# USB_trans.net
KiCad netlist of a schematic drawn in Altium Designer
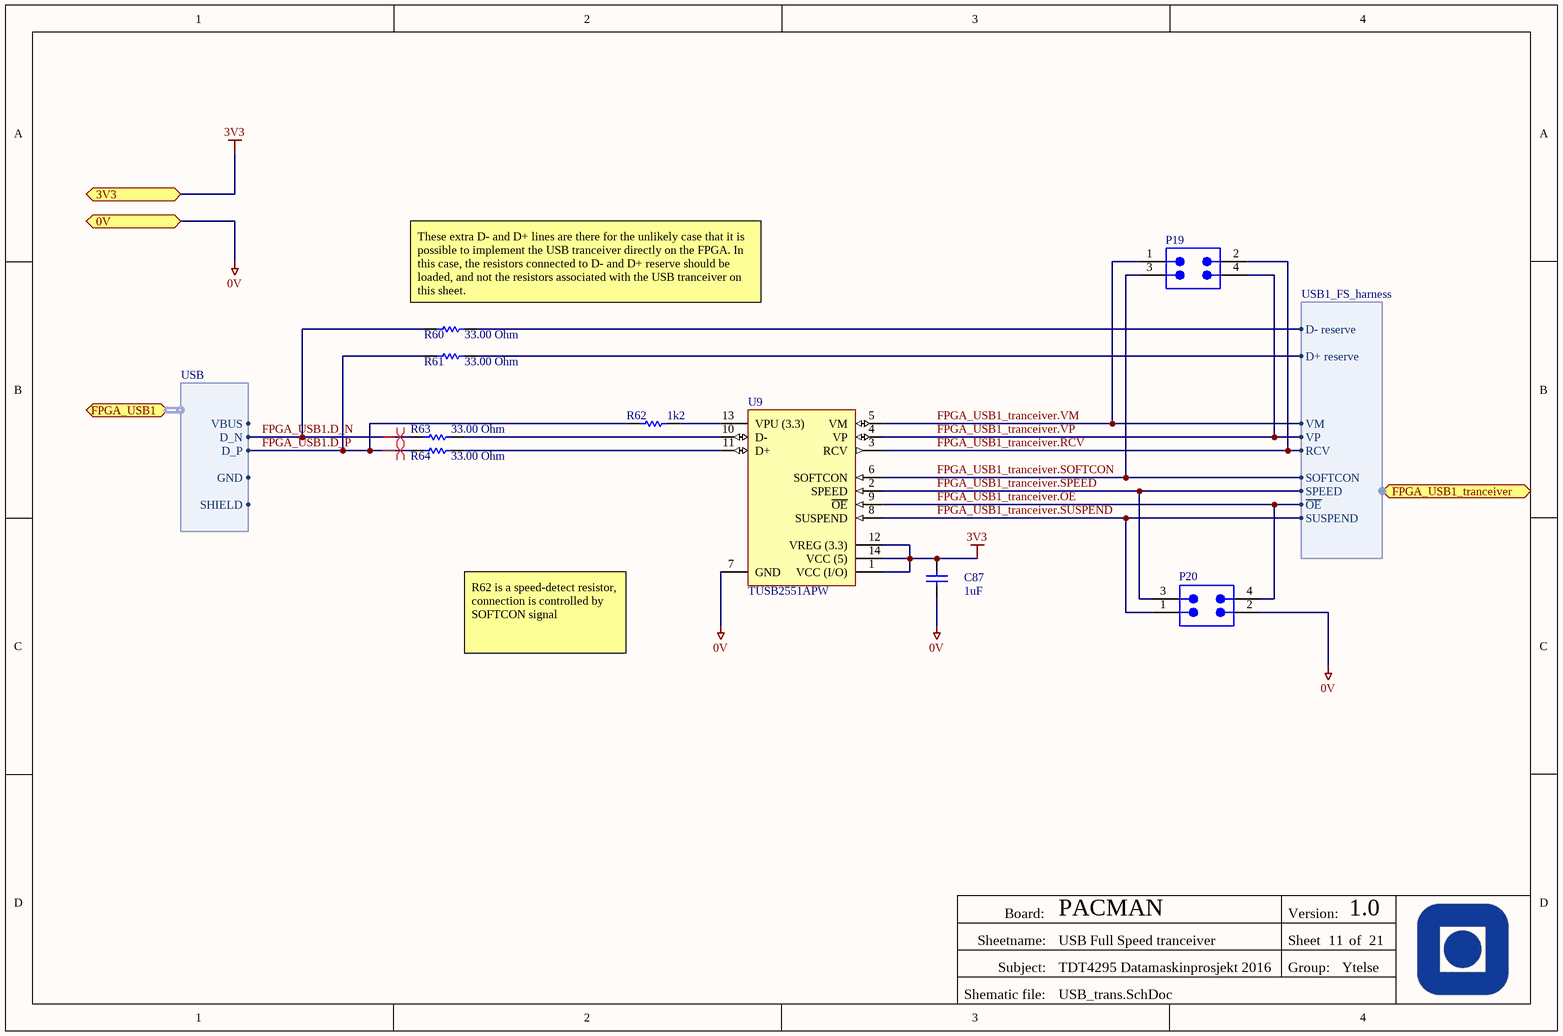
[diagram p0: USB_trans.SchDoc]

(export (version "E")
  (design (tool "Eeschema 10.0.6"))
  (components
    (comp (ref "C87")
      (value "1uF")
      (footprint "CAPC0603(1608)100_N")
      (description "CAP 1uF 16V ±5% 0603 (1608 Metric) Thickness 1mm SMD")
      (fields (field (name "TOLERANCE") "Â±5%") (field (name "Comment") "CAP 1uF 16V 0603(1608)"))
      (libsource (lib "Altium Content Vault") (part "CMP-1035-02736-1"))
    )
    (comp (ref "P19")
      (value "PH2542-4-SPGRH-6-3")
      (footprint "PCE-PH2542-4-SPGRH-6-3_V")
      (description "Male Header, Pitch 2.54mm, 2x2 Position, Mated Height 6mm, Tail Length 3mm")
      (fields (field (name "MANUFACTURER") "Pinchao Electronic"))
      (libsource (lib "") (part "PCE-HDR-2P-M-R4_1"))
    )
    (comp (ref "P20")
      (value "PH2542-4-SPGRH-6-3")
      (footprint "PCE-PH2542-4-SPGRH-6-3_V")
      (description "Male Header, Pitch 2.54mm, 2x2 Position, Mated Height 6mm, Tail Length 3mm")
      (fields (field (name "MANUFACTURER") "Pinchao Electronic"))
      (libsource (lib "Altium Content Vault") (part "PCE-HDR-2P-M-R4"))
    )
    (comp (ref "R60")
      (value "33.00 Ohm")
      (footprint "RESC0603(1608)_M")
      (description "33R 0.1W 5% 0603 (1608 Metric)  SMD")
      (fields (field (name "TOLERANCE") "5 %") (field (name "POWER") "0.1 W"))
      (libsource (lib "Altium Content Vault") (part "CMP-1012-00038-1"))
    )
    (comp (ref "R61")
      (value "33.00 Ohm")
      (footprint "RESC0603(1608)_M")
      (description "33R 0.1W 5% 0603 (1608 Metric)  SMD")
      (fields (field (name "TOLERANCE") "5 %") (field (name "POWER") "0.1 W"))
      (libsource (lib "Altium Content Vault") (part "CMP-1012-00038-1"))
    )
    (comp (ref "R62")
      (value "1k2")
      (footprint "RESC0603(1608)_M")
      (description "1K2 0.1W 1% 0603 (1608 Metric)  SMD")
      (fields (field (name "POWER") "0.1 W") (field (name "TOLERANCE") "1 %"))
      (libsource (lib "Altium Content Vault") (part "CMP-1012-00518-1"))
    )
    (comp (ref "R63")
      (value "33.00 Ohm")
      (footprint "RESC0603(1608)_M")
      (description "33R 0.1W 5% 0603 (1608 Metric)  SMD")
      (fields (field (name "TOLERANCE") "5 %") (field (name "POWER") "0.1 W"))
      (libsource (lib "Altium Content Vault") (part "CMP-1012-00038-1"))
    )
    (comp (ref "R64")
      (value "33.00 Ohm")
      (footprint "RESC0603(1608)_M")
      (description "33R 0.1W 5% 0603 (1608 Metric)  SMD")
      (fields (field (name "TOLERANCE") "5 %") (field (name "POWER") "0.1 W"))
      (libsource (lib "Altium Content Vault") (part "CMP-1012-00038-1"))
    )
    (comp (ref "U9")
      (value "TUSB2551APW")
      (footprint "PW14_N")
      (description "Advanced USB Transceiver, Full Speed, Single, +/-15 KV, -40 to 85 degC, 14-Pin TSSOP (PW)")
      (fields (field (name "MANUFACTURER") "Texas Instruments"))
      (libsource (lib "Altium Content Vault") (part "TI-TUSB2551A-TSSOP_PW-14"))
    )
  )
  (nets
    (net (code "3") (name "/D+ reserve") (class "Default")
      (node (ref "R61") (pin "2") (pinfunction "2_2") (pintype "passive"))
    )
    (net (code "4") (name "/D- reserve") (class "Default")
      (node (ref "R60") (pin "2") (pinfunction "2_2") (pintype "passive"))
    )
    (net (code "5") (name "/FPGA_USB1.D_N") (class "Default")
      (node (ref "R60") (pin "1") (pinfunction "1_1") (pintype "passive"))
      (node (ref "R63") (pin "1") (pinfunction "1_1") (pintype "passive"))
    )
    (net (code "6") (name "/FPGA_USB1.D_P") (class "Default")
      (node (ref "R61") (pin "1") (pinfunction "1_1") (pintype "passive"))
      (node (ref "R62") (pin "1") (pinfunction "1_1") (pintype "passive"))
      (node (ref "R64") (pin "1") (pinfunction "1_1") (pintype "passive"))
    )
    (net (code "7") (name "/FPGA_USB1_tranceiver.RCV") (class "Default")
      (node (ref "P19") (pin "2") (pinfunction "2_2") (pintype "passive"))
      (node (ref "U9") (pin "3") (pinfunction "RCV_3") (pintype "output"))
    )
    (net (code "8") (name "/FPGA_USB1_tranceiver.SOFTCON") (class "Default")
      (node (ref "P19") (pin "3") (pinfunction "3_3") (pintype "passive"))
      (node (ref "U9") (pin "6") (pinfunction "SOFTCON_6") (pintype "input"))
    )
    (net (code "9") (name "/FPGA_USB1_tranceiver.SPEED") (class "Default")
      (node (ref "P20") (pin "3") (pinfunction "3_3") (pintype "passive"))
      (node (ref "U9") (pin "2") (pinfunction "SPEED_2") (pintype "input"))
    )
    (net (code "10") (name "/FPGA_USB1_tranceiver.SUSPEND") (class "Default")
      (node (ref "P20") (pin "1") (pinfunction "1_1") (pintype "passive"))
      (node (ref "U9") (pin "8") (pinfunction "SUSPEND_8") (pintype "input"))
    )
    (net (code "11") (name "/FPGA_USB1_tranceiver.VM") (class "Default")
      (node (ref "P19") (pin "1") (pinfunction "1_1") (pintype "passive"))
      (node (ref "U9") (pin "5") (pinfunction "VM_5") (pintype "bidirectional"))
    )
    (net (code "12") (name "/FPGA_USB1_tranceiver.VP") (class "Default")
      (node (ref "P19") (pin "4") (pinfunction "4_4") (pintype "passive"))
      (node (ref "U9") (pin "4") (pinfunction "VP_4") (pintype "bidirectional"))
    )
    (net (code "13") (name "/FPGA_USB1_tranceiver.~{OE}") (class "Default")
      (node (ref "P20") (pin "4") (pinfunction "4_4") (pintype "passive"))
      (node (ref "U9") (pin "9") (pinfunction "~{OE}_9") (pintype "input"))
    )
    (net (code "16") (name "0V") (class "Default")
      (node (ref "C87") (pin "1") (pinfunction "1_1") (pintype "passive"))
      (node (ref "P20") (pin "2") (pinfunction "2_2") (pintype "passive"))
      (node (ref "U9") (pin "7") (pinfunction "GND_7") (pintype "power_in"))
    )
    (net (code "17") (name "3V3") (class "Default")
      (node (ref "C87") (pin "2") (pinfunction "2_2") (pintype "passive"))
      (node (ref "U9") (pin "1") (pinfunction "VCC_(I/O)_1") (pintype "power_in"))
      (node (ref "U9") (pin "12") (pinfunction "VREG_(3.3)_12") (pintype "power_in"))
      (node (ref "U9") (pin "14") (pinfunction "VCC_(5)_14") (pintype "power_in"))
    )
    (net (code "18") (name "Net-(U9-D+)") (class "Default")
      (node (ref "R64") (pin "2") (pinfunction "2_2") (pintype "passive"))
      (node (ref "U9") (pin "11") (pinfunction "D+_11") (pintype "bidirectional"))
    )
    (net (code "19") (name "Net-(U9-D-)") (class "Default")
      (node (ref "R63") (pin "2") (pinfunction "2_2") (pintype "passive"))
      (node (ref "U9") (pin "10") (pinfunction "D-_10") (pintype "bidirectional"))
    )
    (net (code "20") (name "Net-(U9-VPU_(3.3))") (class "Default")
      (node (ref "R62") (pin "2") (pinfunction "2_2") (pintype "passive"))
      (node (ref "U9") (pin "13") (pinfunction "VPU_(3.3)_13") (pintype "power_in"))
    )
  )
)
